# Sheet1.net
KiCad netlist of a schematic drawn in Altium Designer
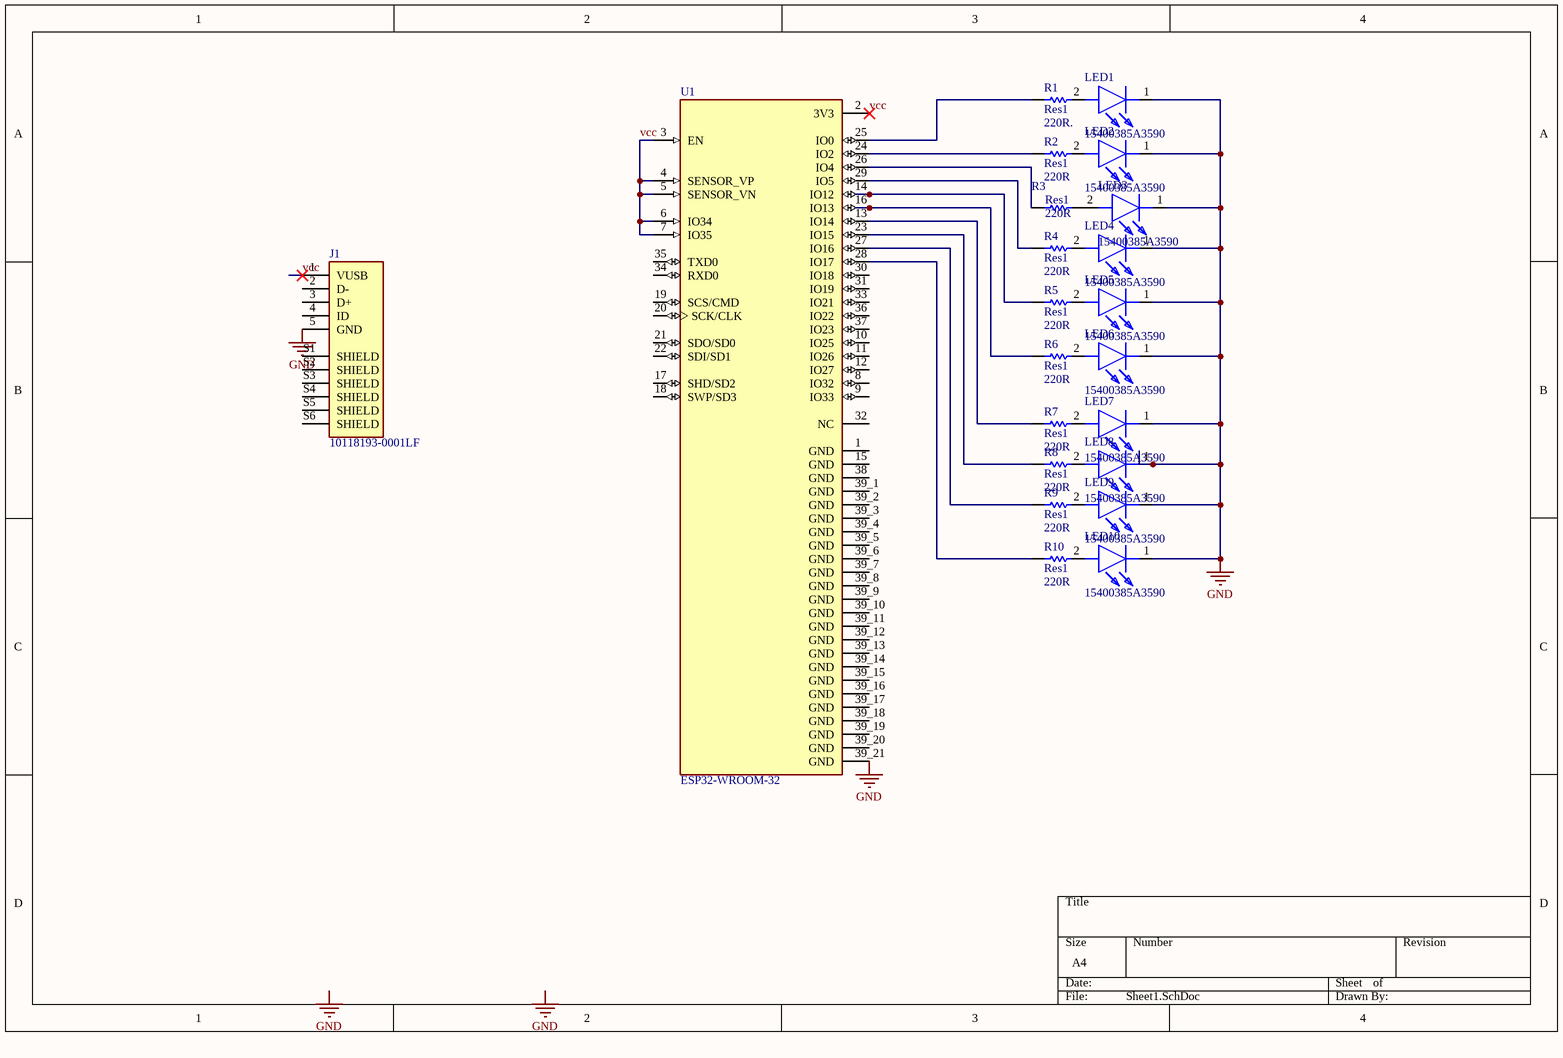
[diagram p0: Sheet1.SchDoc]

(export (version "E")
  (design (tool "Eeschema 10.0.6"))
  (components
    (comp (ref "J1")
      (value "10118193-0001LF")
      (footprint "FCI_10118193-0001LF")
      (description "USB - micro B USB 2.0 Receptacle Connector 5 Position Surface Mount, Right Angle; Through Hole")
      (fields (field (name "MF") "FCI"))
      (libsource (lib "10118193-0001LF") (part "10118193-0001LF"))
    )
    (comp (ref "LED1")
      (value "15400385A3590")
      (footprint "SamacSys:15400385A3590")
      (description "LED")
      (fields (field (name "MOUSER PART NUMBER") "710-15400385A3590"))
      (libsource (lib "SamacSys") (part "15400385A3590"))
    )
    (comp (ref "LED2")
      (value "15400385A3590")
      (footprint "SamacSys:15400385A3590")
      (description "LED")
      (fields (field (name "MOUSER PART NUMBER") "710-15400385A3590"))
      (libsource (lib "SamacSys") (part "15400385A3590"))
    )
    (comp (ref "LED3")
      (value "15400385A3590")
      (footprint "SamacSys:15400385A3590")
      (description "LED")
      (fields (field (name "MOUSER PART NUMBER") "710-15400385A3590"))
      (libsource (lib "SamacSys") (part "15400385A3590"))
    )
    (comp (ref "LED4")
      (value "15400385A3590")
      (footprint "SamacSys:15400385A3590")
      (description "LED")
      (fields (field (name "MOUSER PART NUMBER") "710-15400385A3590"))
      (libsource (lib "SamacSys") (part "15400385A3590"))
    )
    (comp (ref "LED5")
      (value "15400385A3590")
      (footprint "SamacSys:15400385A3590")
      (description "LED")
      (fields (field (name "MOUSER PART NUMBER") "710-15400385A3590"))
      (libsource (lib "SamacSys") (part "15400385A3590"))
    )
    (comp (ref "LED6")
      (value "15400385A3590")
      (footprint "SamacSys:15400385A3590")
      (description "LED")
      (fields (field (name "MOUSER PART NUMBER") "710-15400385A3590"))
      (libsource (lib "SamacSys") (part "15400385A3590"))
    )
    (comp (ref "LED7")
      (value "15400385A3590")
      (footprint "SamacSys:15400385A3590")
      (description "LED")
      (fields (field (name "MOUSER PART NUMBER") "710-15400385A3590"))
      (libsource (lib "SamacSys") (part "15400385A3590"))
    )
    (comp (ref "LED8")
      (value "15400385A3590")
      (footprint "SamacSys:15400385A3590")
      (description "LED")
      (fields (field (name "MOUSER PART NUMBER") "710-15400385A3590"))
      (libsource (lib "SamacSys") (part "15400385A3590"))
    )
    (comp (ref "LED9")
      (value "15400385A3590")
      (footprint "SamacSys:15400385A3590")
      (description "LED")
      (fields (field (name "MOUSER PART NUMBER") "710-15400385A3590"))
      (libsource (lib "SamacSys") (part "15400385A3590"))
    )
    (comp (ref "LED10")
      (value "15400385A3590")
      (footprint "SamacSys:15400385A3590")
      (description "LED")
      (fields (field (name "MOUSER PART NUMBER") "710-15400385A3590"))
      (libsource (lib "SamacSys") (part "15400385A3590"))
    )
    (comp (ref "R1")
      (value "Res1")
      (footprint "AXIAL-0.3")
      (description "Resistor")
      (fields (field (name "ALTIUM_VALUE") "220R.") (field (name "PUBLISHER") "Altium Limited"))
      (libsource (lib "Miscellaneous Devices") (part "Res1"))
    )
    (comp (ref "R2")
      (value "Res1")
      (footprint "AXIAL-0.3")
      (description "Resistor")
      (fields (field (name "ALTIUM_VALUE") "220R") (field (name "PUBLISHER") "Altium Limited"))
      (libsource (lib "Miscellaneous Devices") (part "Res1"))
    )
    (comp (ref "R3")
      (value "Res1")
      (footprint "AXIAL-0.3")
      (description "Resistor")
      (fields (field (name "ALTIUM_VALUE") "220R") (field (name "PUBLISHER") "Altium Limited"))
      (libsource (lib "Miscellaneous Devices") (part "Res1"))
    )
    (comp (ref "R4")
      (value "Res1")
      (footprint "AXIAL-0.3")
      (description "Resistor")
      (fields (field (name "ALTIUM_VALUE") "220R") (field (name "PUBLISHER") "Altium Limited"))
      (libsource (lib "Miscellaneous Devices") (part "Res1"))
    )
    (comp (ref "R5")
      (value "Res1")
      (footprint "AXIAL-0.3")
      (description "Resistor")
      (fields (field (name "ALTIUM_VALUE") "220R") (field (name "PUBLISHER") "Altium Limited"))
      (libsource (lib "Miscellaneous Devices") (part "Res1"))
    )
    (comp (ref "R6")
      (value "Res1")
      (footprint "AXIAL-0.3")
      (description "Resistor")
      (fields (field (name "ALTIUM_VALUE") "220R") (field (name "PUBLISHER") "Altium Limited"))
      (libsource (lib "Miscellaneous Devices") (part "Res1"))
    )
    (comp (ref "R7")
      (value "Res1")
      (footprint "AXIAL-0.3")
      (description "Resistor")
      (fields (field (name "ALTIUM_VALUE") "220R") (field (name "PUBLISHER") "Altium Limited"))
      (libsource (lib "Miscellaneous Devices") (part "Res1"))
    )
    (comp (ref "R8")
      (value "Res1")
      (footprint "AXIAL-0.3")
      (description "Resistor")
      (fields (field (name "ALTIUM_VALUE") "220R") (field (name "PUBLISHER") "Altium Limited"))
      (libsource (lib "Miscellaneous Devices") (part "Res1"))
    )
    (comp (ref "R9")
      (value "Res1")
      (footprint "AXIAL-0.3")
      (description "Resistor")
      (fields (field (name "ALTIUM_VALUE") "220R") (field (name "PUBLISHER") "Altium Limited"))
      (libsource (lib "Miscellaneous Devices") (part "Res1"))
    )
    (comp (ref "R10")
      (value "Res1")
      (footprint "AXIAL-0.3")
      (description "Resistor")
      (fields (field (name "ALTIUM_VALUE") "220R") (field (name "PUBLISHER") "Altium Limited"))
      (libsource (lib "Miscellaneous Devices") (part "Res1"))
    )
    (comp (ref "U1")
      (value "ESP32-WROOM-32")
      (footprint "MODULE_ESP32-WROOM-32")
      (fields (field (name "MF") "Espressif Systems"))
      (libsource (lib "ESP32-WROOM-32") (part "ESP32-WROOM-32"))
    )
  )
  (nets
    (net (code "1") (name "/vcc") (class "Default")
      (node (ref "J1") (pin "1") (pinfunction "VUSB_1") (pintype "passive"))
      (node (ref "U1") (pin "2") (pinfunction "3V3_2") (pintype "power_in"))
      (node (ref "U1") (pin "3") (pinfunction "EN_3") (pintype "input"))
      (node (ref "U1") (pin "4") (pinfunction "SENSOR_VP_4") (pintype "input"))
      (node (ref "U1") (pin "5") (pinfunction "SENSOR_VN_5") (pintype "input"))
      (node (ref "U1") (pin "6") (pinfunction "IO34_6") (pintype "input"))
      (node (ref "U1") (pin "7") (pinfunction "IO35_7") (pintype "input"))
    )
    (net (code "2") (name "GND") (class "Default")
      (node (ref "J1") (pin "5") (pinfunction "GND_5") (pintype "passive"))
      (node (ref "LED1") (pin "1") (pinfunction "K_1") (pintype "passive"))
      (node (ref "LED10") (pin "1") (pinfunction "K_1") (pintype "passive"))
      (node (ref "LED2") (pin "1") (pinfunction "K_1") (pintype "passive"))
      (node (ref "LED3") (pin "1") (pinfunction "K_1") (pintype "passive"))
      (node (ref "LED4") (pin "1") (pinfunction "K_1") (pintype "passive"))
      (node (ref "LED5") (pin "1") (pinfunction "K_1") (pintype "passive"))
      (node (ref "LED6") (pin "1") (pinfunction "K_1") (pintype "passive"))
      (node (ref "LED7") (pin "1") (pinfunction "K_1") (pintype "passive"))
      (node (ref "LED8") (pin "1") (pinfunction "K_1") (pintype "passive"))
      (node (ref "LED9") (pin "1") (pinfunction "K_1") (pintype "passive"))
      (node (ref "U1") (pin "39_21") (pinfunction "GND_39_21") (pintype "power_in"))
    )
    (net (code "3") (name "Net-(LED3-A)") (class "Default")
      (node (ref "LED3") (pin "2") (pinfunction "A_2") (pintype "passive"))
      (node (ref "R3") (pin "2") (pinfunction "2_2") (pintype "passive"))
    )
    (net (code "4") (name "Net-(U1-IO0)") (class "Default")
      (node (ref "R1") (pin "1") (pinfunction "1_1") (pintype "passive"))
      (node (ref "U1") (pin "25") (pinfunction "IO0_25") (pintype "bidirectional"))
    )
    (net (code "5") (name "Net-(U1-IO2)") (class "Default")
      (node (ref "R2") (pin "1") (pinfunction "1_1") (pintype "passive"))
      (node (ref "U1") (pin "24") (pinfunction "IO2_24") (pintype "bidirectional"))
    )
    (net (code "6") (name "Net-(U1-IO4)") (class "Default")
      (node (ref "R3") (pin "1") (pinfunction "1_1") (pintype "passive"))
      (node (ref "U1") (pin "26") (pinfunction "IO4_26") (pintype "bidirectional"))
    )
    (net (code "7") (name "Net-(U1-IO5)") (class "Default")
      (node (ref "R4") (pin "1") (pinfunction "1_1") (pintype "passive"))
      (node (ref "U1") (pin "29") (pinfunction "IO5_29") (pintype "bidirectional"))
    )
    (net (code "8") (name "Net-(U1-IO12)") (class "Default")
      (node (ref "R5") (pin "1") (pinfunction "1_1") (pintype "passive"))
      (node (ref "U1") (pin "14") (pinfunction "IO12_14") (pintype "bidirectional"))
    )
    (net (code "9") (name "Net-(U1-IO13)") (class "Default")
      (node (ref "R6") (pin "1") (pinfunction "1_1") (pintype "passive"))
      (node (ref "U1") (pin "16") (pinfunction "IO13_16") (pintype "bidirectional"))
    )
    (net (code "10") (name "Net-(U1-IO14)") (class "Default")
      (node (ref "R7") (pin "1") (pinfunction "1_1") (pintype "passive"))
      (node (ref "U1") (pin "13") (pinfunction "IO14_13") (pintype "bidirectional"))
    )
    (net (code "11") (name "Net-(U1-IO15)") (class "Default")
      (node (ref "R8") (pin "1") (pinfunction "1_1") (pintype "passive"))
      (node (ref "U1") (pin "23") (pinfunction "IO15_23") (pintype "bidirectional"))
    )
    (net (code "12") (name "Net-(U1-IO16)") (class "Default")
      (node (ref "R9") (pin "1") (pinfunction "1_1") (pintype "passive"))
      (node (ref "U1") (pin "27") (pinfunction "IO16_27") (pintype "bidirectional"))
    )
    (net (code "13") (name "Net-(U1-IO17)") (class "Default")
      (node (ref "R10") (pin "1") (pinfunction "1_1") (pintype "passive"))
      (node (ref "U1") (pin "28") (pinfunction "IO17_28") (pintype "bidirectional"))
    )
    (net (code "14") (name "unconnected-(J1-D+-Pad3)") (class "Default")
      (node (ref "J1") (pin "3") (pinfunction "D+_3") (pintype "passive"))
    )
    (net (code "15") (name "unconnected-(J1-D--Pad2)") (class "Default")
      (node (ref "J1") (pin "2") (pinfunction "D-_2") (pintype "passive"))
    )
    (net (code "16") (name "unconnected-(J1-ID-Pad4)") (class "Default")
      (node (ref "J1") (pin "4") (pinfunction "ID_4") (pintype "passive"))
    )
    (net (code "17") (name "unconnected-(J1-SHIELD-PadS1)") (class "Default")
      (node (ref "J1") (pin "S1") (pinfunction "SHIELD_S1") (pintype "passive"))
    )
    (net (code "18") (name "unconnected-(J1-SHIELD-PadS2)") (class "Default")
      (node (ref "J1") (pin "S2") (pinfunction "SHIELD_S2") (pintype "passive"))
    )
    (net (code "19") (name "unconnected-(J1-SHIELD-PadS3)") (class "Default")
      (node (ref "J1") (pin "S3") (pinfunction "SHIELD_S3") (pintype "passive"))
    )
    (net (code "20") (name "unconnected-(J1-SHIELD-PadS4)") (class "Default")
      (node (ref "J1") (pin "S4") (pinfunction "SHIELD_S4") (pintype "passive"))
    )
    (net (code "21") (name "unconnected-(J1-SHIELD-PadS5)") (class "Default")
      (node (ref "J1") (pin "S5") (pinfunction "SHIELD_S5") (pintype "passive"))
    )
    (net (code "22") (name "unconnected-(J1-SHIELD-PadS6)") (class "Default")
      (node (ref "J1") (pin "S6") (pinfunction "SHIELD_S6") (pintype "passive"))
    )
    (net (code "23") (name "unconnected-(LED1-A-Pad2)") (class "Default")
      (node (ref "LED1") (pin "2") (pinfunction "A_2") (pintype "passive"))
    )
    (net (code "24") (name "unconnected-(LED2-A-Pad2)") (class "Default")
      (node (ref "LED2") (pin "2") (pinfunction "A_2") (pintype "passive"))
    )
    (net (code "25") (name "unconnected-(LED4-A-Pad2)") (class "Default")
      (node (ref "LED4") (pin "2") (pinfunction "A_2") (pintype "passive"))
    )
    (net (code "26") (name "unconnected-(LED5-A-Pad2)") (class "Default")
      (node (ref "LED5") (pin "2") (pinfunction "A_2") (pintype "passive"))
    )
    (net (code "27") (name "unconnected-(LED6-A-Pad2)") (class "Default")
      (node (ref "LED6") (pin "2") (pinfunction "A_2") (pintype "passive"))
    )
    (net (code "28") (name "unconnected-(LED7-A-Pad2)") (class "Default")
      (node (ref "LED7") (pin "2") (pinfunction "A_2") (pintype "passive"))
    )
    (net (code "29") (name "unconnected-(LED8-A-Pad2)") (class "Default")
      (node (ref "LED8") (pin "2") (pinfunction "A_2") (pintype "passive"))
    )
    (net (code "30") (name "unconnected-(LED9-A-Pad2)") (class "Default")
      (node (ref "LED9") (pin "2") (pinfunction "A_2") (pintype "passive"))
    )
    (net (code "31") (name "unconnected-(LED10-A-Pad2)") (class "Default")
      (node (ref "LED10") (pin "2") (pinfunction "A_2") (pintype "passive"))
    )
    (net (code "32") (name "unconnected-(R1-Pad2)") (class "Default")
      (node (ref "R1") (pin "2") (pinfunction "2_2") (pintype "passive"))
    )
    (net (code "33") (name "unconnected-(R2-Pad2)") (class "Default")
      (node (ref "R2") (pin "2") (pinfunction "2_2") (pintype "passive"))
    )
    (net (code "34") (name "unconnected-(R4-Pad2)") (class "Default")
      (node (ref "R4") (pin "2") (pinfunction "2_2") (pintype "passive"))
    )
    (net (code "35") (name "unconnected-(R5-Pad2)") (class "Default")
      (node (ref "R5") (pin "2") (pinfunction "2_2") (pintype "passive"))
    )
    (net (code "36") (name "unconnected-(R6-Pad2)") (class "Default")
      (node (ref "R6") (pin "2") (pinfunction "2_2") (pintype "passive"))
    )
    (net (code "37") (name "unconnected-(R7-Pad2)") (class "Default")
      (node (ref "R7") (pin "2") (pinfunction "2_2") (pintype "passive"))
    )
    (net (code "38") (name "unconnected-(R8-Pad2)") (class "Default")
      (node (ref "R8") (pin "2") (pinfunction "2_2") (pintype "passive"))
    )
    (net (code "39") (name "unconnected-(R9-Pad2)") (class "Default")
      (node (ref "R9") (pin "2") (pinfunction "2_2") (pintype "passive"))
    )
    (net (code "40") (name "unconnected-(R10-Pad2)") (class "Default")
      (node (ref "R10") (pin "2") (pinfunction "2_2") (pintype "passive"))
    )
    (net (code "41") (name "unconnected-(U1-GND-Pad1)") (class "Default")
      (node (ref "U1") (pin "1") (pinfunction "GND_1") (pintype "power_in"))
    )
    (net (code "42") (name "unconnected-(U1-GND-Pad15)") (class "Default")
      (node (ref "U1") (pin "15") (pinfunction "GND_15") (pintype "power_in"))
    )
    (net (code "43") (name "unconnected-(U1-GND-Pad38)") (class "Default")
      (node (ref "U1") (pin "38") (pinfunction "GND_38") (pintype "power_in"))
    )
    (net (code "44") (name "unconnected-(U1-GND-Pad39_1)") (class "Default")
      (node (ref "U1") (pin "39_1") (pinfunction "GND_39_1") (pintype "power_in"))
    )
    (net (code "45") (name "unconnected-(U1-GND-Pad39_2)") (class "Default")
      (node (ref "U1") (pin "39_2") (pinfunction "GND_39_2") (pintype "power_in"))
    )
    (net (code "46") (name "unconnected-(U1-GND-Pad39_3)") (class "Default")
      (node (ref "U1") (pin "39_3") (pinfunction "GND_39_3") (pintype "power_in"))
    )
    (net (code "47") (name "unconnected-(U1-GND-Pad39_4)") (class "Default")
      (node (ref "U1") (pin "39_4") (pinfunction "GND_39_4") (pintype "power_in"))
    )
    (net (code "48") (name "unconnected-(U1-GND-Pad39_5)") (class "Default")
      (node (ref "U1") (pin "39_5") (pinfunction "GND_39_5") (pintype "power_in"))
    )
    (net (code "49") (name "unconnected-(U1-GND-Pad39_6)") (class "Default")
      (node (ref "U1") (pin "39_6") (pinfunction "GND_39_6") (pintype "power_in"))
    )
    (net (code "50") (name "unconnected-(U1-GND-Pad39_7)") (class "Default")
      (node (ref "U1") (pin "39_7") (pinfunction "GND_39_7") (pintype "power_in"))
    )
    (net (code "51") (name "unconnected-(U1-GND-Pad39_8)") (class "Default")
      (node (ref "U1") (pin "39_8") (pinfunction "GND_39_8") (pintype "power_in"))
    )
    (net (code "52") (name "unconnected-(U1-GND-Pad39_9)") (class "Default")
      (node (ref "U1") (pin "39_9") (pinfunction "GND_39_9") (pintype "power_in"))
    )
    (net (code "53") (name "unconnected-(U1-GND-Pad39_10)") (class "Default")
      (node (ref "U1") (pin "39_10") (pinfunction "GND_39_10") (pintype "power_in"))
    )
    (net (code "54") (name "unconnected-(U1-GND-Pad39_11)") (class "Default")
      (node (ref "U1") (pin "39_11") (pinfunction "GND_39_11") (pintype "power_in"))
    )
    (net (code "55") (name "unconnected-(U1-GND-Pad39_12)") (class "Default")
      (node (ref "U1") (pin "39_12") (pinfunction "GND_39_12") (pintype "power_in"))
    )
    (net (code "56") (name "unconnected-(U1-GND-Pad39_13)") (class "Default")
      (node (ref "U1") (pin "39_13") (pinfunction "GND_39_13") (pintype "power_in"))
    )
    (net (code "57") (name "unconnected-(U1-GND-Pad39_14)") (class "Default")
      (node (ref "U1") (pin "39_14") (pinfunction "GND_39_14") (pintype "power_in"))
    )
    (net (code "58") (name "unconnected-(U1-GND-Pad39_15)") (class "Default")
      (node (ref "U1") (pin "39_15") (pinfunction "GND_39_15") (pintype "power_in"))
    )
    (net (code "59") (name "unconnected-(U1-GND-Pad39_16)") (class "Default")
      (node (ref "U1") (pin "39_16") (pinfunction "GND_39_16") (pintype "power_in"))
    )
    (net (code "60") (name "unconnected-(U1-GND-Pad39_17)") (class "Default")
      (node (ref "U1") (pin "39_17") (pinfunction "GND_39_17") (pintype "power_in"))
    )
    (net (code "61") (name "unconnected-(U1-GND-Pad39_18)") (class "Default")
      (node (ref "U1") (pin "39_18") (pinfunction "GND_39_18") (pintype "power_in"))
    )
    (net (code "62") (name "unconnected-(U1-GND-Pad39_19)") (class "Default")
      (node (ref "U1") (pin "39_19") (pinfunction "GND_39_19") (pintype "power_in"))
    )
    (net (code "63") (name "unconnected-(U1-GND-Pad39_20)") (class "Default")
      (node (ref "U1") (pin "39_20") (pinfunction "GND_39_20") (pintype "power_in"))
    )
    (net (code "64") (name "unconnected-(U1-IO18-Pad30)") (class "Default")
      (node (ref "U1") (pin "30") (pinfunction "IO18_30") (pintype "bidirectional"))
    )
    (net (code "65") (name "unconnected-(U1-IO19-Pad31)") (class "Default")
      (node (ref "U1") (pin "31") (pinfunction "IO19_31") (pintype "bidirectional"))
    )
    (net (code "66") (name "unconnected-(U1-IO21-Pad33)") (class "Default")
      (node (ref "U1") (pin "33") (pinfunction "IO21_33") (pintype "bidirectional"))
    )
    (net (code "67") (name "unconnected-(U1-IO22-Pad36)") (class "Default")
      (node (ref "U1") (pin "36") (pinfunction "IO22_36") (pintype "bidirectional"))
    )
    (net (code "68") (name "unconnected-(U1-IO23-Pad37)") (class "Default")
      (node (ref "U1") (pin "37") (pinfunction "IO23_37") (pintype "bidirectional"))
    )
    (net (code "69") (name "unconnected-(U1-IO25-Pad10)") (class "Default")
      (node (ref "U1") (pin "10") (pinfunction "IO25_10") (pintype "bidirectional"))
    )
    (net (code "70") (name "unconnected-(U1-IO26-Pad11)") (class "Default")
      (node (ref "U1") (pin "11") (pinfunction "IO26_11") (pintype "bidirectional"))
    )
    (net (code "71") (name "unconnected-(U1-IO27-Pad12)") (class "Default")
      (node (ref "U1") (pin "12") (pinfunction "IO27_12") (pintype "bidirectional"))
    )
    (net (code "72") (name "unconnected-(U1-IO32-Pad8)") (class "Default")
      (node (ref "U1") (pin "8") (pinfunction "IO32_8") (pintype "bidirectional"))
    )
    (net (code "73") (name "unconnected-(U1-IO33-Pad9)") (class "Default")
      (node (ref "U1") (pin "9") (pinfunction "IO33_9") (pintype "bidirectional"))
    )
    (net (code "74") (name "unconnected-(U1-NC-Pad32)") (class "Default")
      (node (ref "U1") (pin "32") (pinfunction "NC_32") (pintype "passive"))
    )
    (net (code "75") (name "unconnected-(U1-RXD0-Pad34)") (class "Default")
      (node (ref "U1") (pin "34") (pinfunction "RXD0_34") (pintype "bidirectional"))
    )
    (net (code "76") (name "unconnected-(U1-SCK{slash}CLK-Pad20)") (class "Default")
      (node (ref "U1") (pin "20") (pinfunction "SCK/CLK_20") (pintype "bidirectional"))
    )
    (net (code "77") (name "unconnected-(U1-SCS{slash}CMD-Pad19)") (class "Default")
      (node (ref "U1") (pin "19") (pinfunction "SCS/CMD_19") (pintype "bidirectional"))
    )
    (net (code "78") (name "unconnected-(U1-SDI{slash}SD1-Pad22)") (class "Default")
      (node (ref "U1") (pin "22") (pinfunction "SDI/SD1_22") (pintype "bidirectional"))
    )
    (net (code "79") (name "unconnected-(U1-SDO{slash}SD0-Pad21)") (class "Default")
      (node (ref "U1") (pin "21") (pinfunction "SDO/SD0_21") (pintype "bidirectional"))
    )
    (net (code "80") (name "unconnected-(U1-SHD{slash}SD2-Pad17)") (class "Default")
      (node (ref "U1") (pin "17") (pinfunction "SHD/SD2_17") (pintype "bidirectional"))
    )
    (net (code "81") (name "unconnected-(U1-SWP{slash}SD3-Pad18)") (class "Default")
      (node (ref "U1") (pin "18") (pinfunction "SWP/SD3_18") (pintype "bidirectional"))
    )
    (net (code "82") (name "unconnected-(U1-TXD0-Pad35)") (class "Default")
      (node (ref "U1") (pin "35") (pinfunction "TXD0_35") (pintype "bidirectional"))
    )
  )
)
